# motorboard.net
KiCad netlist of a schematic drawn in EAGLE
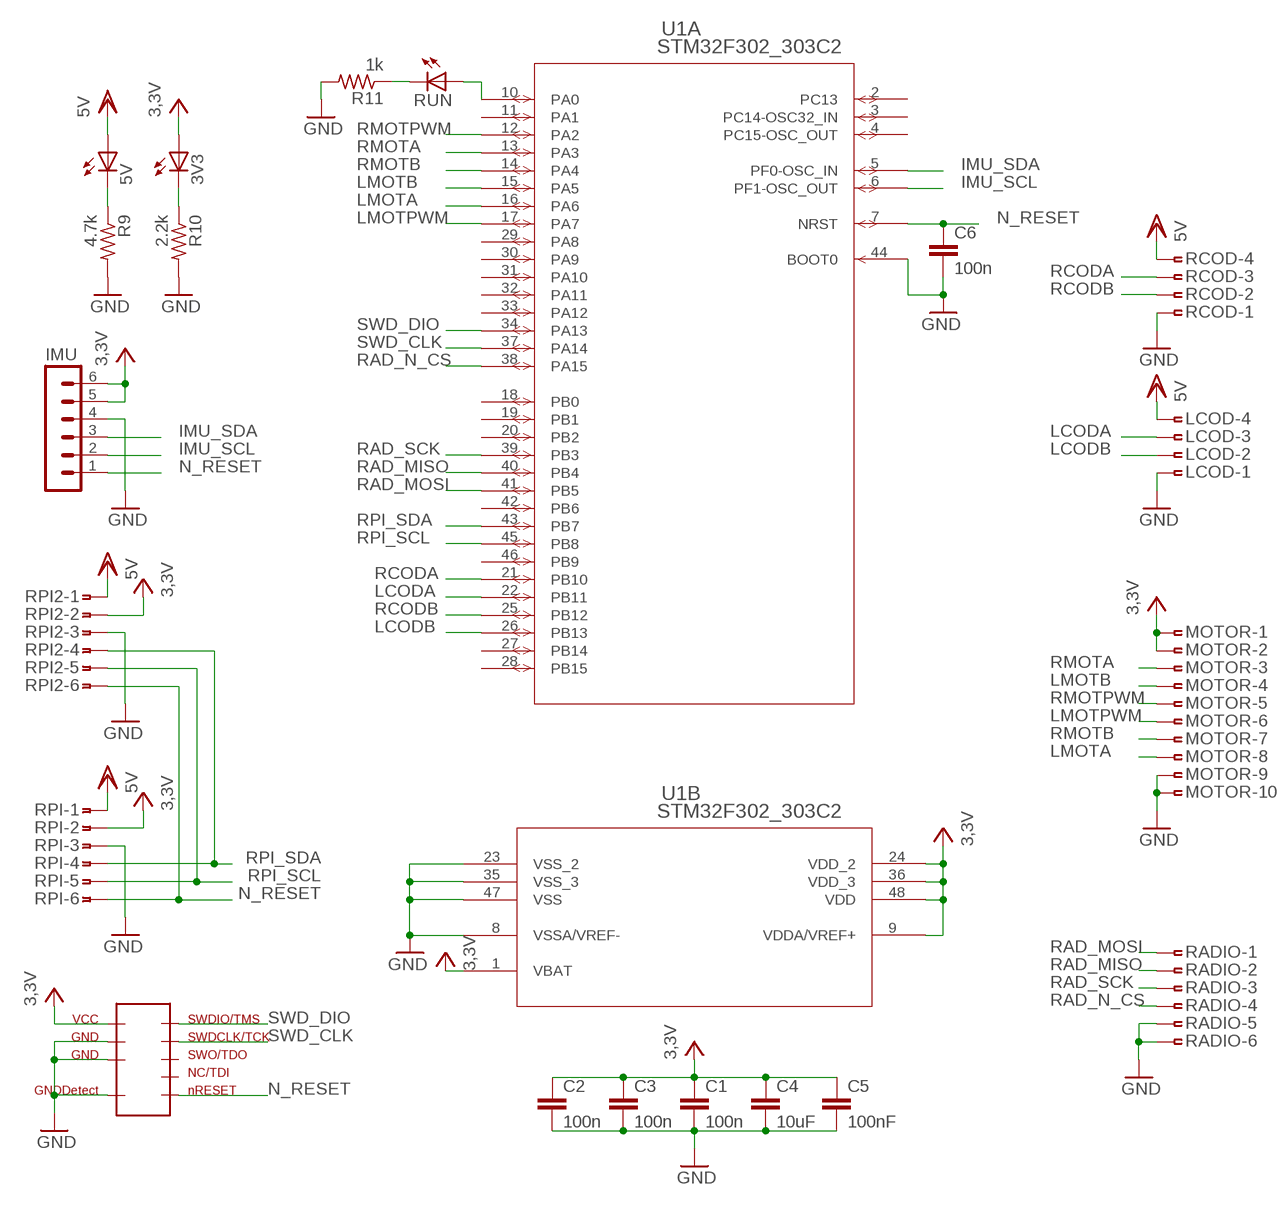
[diagram p0: schematic, sheet 1]

(export (version "E")
  (design (tool "Eeschema 10.0.6"))
  (components
    (comp (ref "3V3")
      (value "LEDCHIPLED_0805")
      (footprint "eagle-import:CHIPLED_0805")
      (libsource (lib "eagle-import") (part "LEDCHIPLED_0805"))
    )
    (comp (ref "5V")
      (value "LEDCHIPLED_0805")
      (footprint "eagle-import:CHIPLED_0805")
      (libsource (lib "eagle-import") (part "LEDCHIPLED_0805"))
    )
    (comp (ref "C1")
      (value "100n")
      (footprint "eagle-import:C0805")
      (libsource (lib "eagle-import") (part "C-EUC0805"))
    )
    (comp (ref "C2")
      (value "100n")
      (footprint "eagle-import:C0805")
      (libsource (lib "eagle-import") (part "C-EUC0805"))
    )
    (comp (ref "C3")
      (value "100n")
      (footprint "eagle-import:C0805")
      (libsource (lib "eagle-import") (part "C-EUC0805"))
    )
    (comp (ref "C4")
      (value "10uF")
      (footprint "eagle-import:C0805")
      (libsource (lib "eagle-import") (part "C-EUC0805"))
    )
    (comp (ref "C5")
      (value "100nF")
      (footprint "eagle-import:C0805")
      (libsource (lib "eagle-import") (part "C-EUC0805"))
    )
    (comp (ref "C6")
      (value "100n")
      (footprint "eagle-import:C0805")
      (libsource (lib "eagle-import") (part "C-EUC0805"))
    )
    (comp (ref "IMU")
      (value "MA06-1")
      (footprint "eagle-import:MA06-1")
      (libsource (lib "eagle-import") (part "MA06-1"))
    )
    (comp (ref "LCOD")
      (value "SMDTOP-4")
      (footprint "eagle-import:SMDTOP4")
      (libsource (lib "eagle-import") (part "SMDTOP-4"))
    )
    (comp (ref "MOTOR")
      (value "SMDTOP-10")
      (footprint "eagle-import:SMDTOP10")
      (libsource (lib "eagle-import") (part "SMDTOP-10"))
    )
    (comp (ref "R9")
      (value "4.7k")
      (footprint "eagle-import:M0805")
      (libsource (lib "eagle-import") (part "R-US_M0805"))
    )
    (comp (ref "R10")
      (value "2.2k")
      (footprint "eagle-import:M0805")
      (libsource (lib "eagle-import") (part "R-US_M0805"))
    )
    (comp (ref "R11")
      (value "1k")
      (footprint "eagle-import:M0805")
      (libsource (lib "eagle-import") (part "R-US_M0805"))
    )
    (comp (ref "RADIO")
      (value "SMDTOP-6")
      (footprint "eagle-import:SMDTOP6")
      (libsource (lib "eagle-import") (part "SMDTOP-6"))
    )
    (comp (ref "RCOD")
      (value "SMDTOP-4")
      (footprint "eagle-import:SMDTOP4")
      (libsource (lib "eagle-import") (part "SMDTOP-4"))
    )
    (comp (ref "RPI")
      (value "SMDTOP-6")
      (footprint "eagle-import:SMDTOP6")
      (libsource (lib "eagle-import") (part "SMDTOP-6"))
    )
    (comp (ref "RPI2")
      (value "SMDTOP-6")
      (footprint "eagle-import:SMDTOP6")
      (libsource (lib "eagle-import") (part "SMDTOP-6"))
    )
    (comp (ref "RUN")
      (value "LEDCHIPLED_0805")
      (footprint "eagle-import:CHIPLED_0805")
      (libsource (lib "eagle-import") (part "LEDCHIPLED_0805"))
    )
    (comp (ref "U$1")
      (value "SWD/JTAG-_PINS")
      (footprint "eagle-import:SAMTEC_SHF-105-01-L-D-SM")
      (libsource (lib "eagle-import") (part "SWD/JTAG-_PINS"))
    )
    (comp (ref "U1")
      (value "STM32F302_303C2")
      (footprint "eagle-import:LQFP48-7X7MM")
      (fields
        (field (name "MANUFACTURER_PART_NUMBER") "stm32f302_303c2")
        (field (name "COPYRIGHT") "Copyright C 2016 Accelerated Designs. All rights reserved")
      )
      (libsource (lib "eagle-import") (part "STM32F302_303C2"))
    )
  )
  (nets
    (net (code "1") (name "/IMU_SCL") (class "Default")
      (node (ref "IMU") (pin "2") (pinfunction "2_2") (pintype "passive"))
      (node (ref "U1") (pin "6") (pinfunction "PF1-OSC_OUT_6") (pintype "bidirectional"))
    )
    (net (code "2") (name "/IMU_SDA") (class "Default")
      (node (ref "IMU") (pin "3") (pinfunction "3_3") (pintype "passive"))
      (node (ref "U1") (pin "5") (pinfunction "PF0-OSC_IN_5") (pintype "bidirectional"))
    )
    (net (code "3") (name "/LCODA") (class "Default")
      (node (ref "LCOD") (pin "3") (pinfunction "1_3") (pintype "passive"))
      (node (ref "U1") (pin "22") (pinfunction "PB11_22") (pintype "bidirectional"))
    )
    (net (code "4") (name "/LCODB") (class "Default")
      (node (ref "LCOD") (pin "2") (pinfunction "1_2") (pintype "passive"))
      (node (ref "U1") (pin "26") (pinfunction "PB13_26") (pintype "bidirectional"))
    )
    (net (code "5") (name "/LMOTA") (class "Default")
      (node (ref "MOTOR") (pin "8") (pinfunction "1_8") (pintype "passive"))
      (node (ref "U1") (pin "16") (pinfunction "PA6_16") (pintype "bidirectional"))
    )
    (net (code "6") (name "/LMOTB") (class "Default")
      (node (ref "MOTOR") (pin "4") (pinfunction "1_4") (pintype "passive"))
      (node (ref "U1") (pin "15") (pinfunction "PA5_15") (pintype "bidirectional"))
    )
    (net (code "7") (name "/LMOTPWM") (class "Default")
      (node (ref "MOTOR") (pin "6") (pinfunction "1_6") (pintype "passive"))
      (node (ref "U1") (pin "17") (pinfunction "PA7_17") (pintype "bidirectional"))
    )
    (net (code "8") (name "/N_RESET") (class "Default")
      (node (ref "C6") (pin "1") (pinfunction "1_1") (pintype "passive"))
      (node (ref "IMU") (pin "1") (pinfunction "1_1") (pintype "passive"))
      (node (ref "RPI") (pin "6") (pinfunction "1_6") (pintype "passive"))
      (node (ref "RPI2") (pin "6") (pinfunction "1_6") (pintype "passive"))
      (node (ref "U$1") (pin "P$10") (pinfunction "P$10_P$10") (pintype "bidirectional"))
      (node (ref "U1") (pin "7") (pinfunction "NRST_7") (pintype "bidirectional"))
    )
    (net (code "9") (name "/RAD_MISO") (class "Default")
      (node (ref "RADIO") (pin "2") (pinfunction "1_2") (pintype "passive"))
      (node (ref "U1") (pin "40") (pinfunction "PB4_40") (pintype "bidirectional"))
    )
    (net (code "10") (name "/RAD_MOSI") (class "Default")
      (node (ref "RADIO") (pin "1") (pinfunction "1_1") (pintype "passive"))
      (node (ref "U1") (pin "41") (pinfunction "PB5_41") (pintype "bidirectional"))
    )
    (net (code "11") (name "/RAD_N_CS") (class "Default")
      (node (ref "RADIO") (pin "4") (pinfunction "1_4") (pintype "passive"))
      (node (ref "U1") (pin "38") (pinfunction "PA15_38") (pintype "bidirectional"))
    )
    (net (code "12") (name "/RAD_SCK") (class "Default")
      (node (ref "RADIO") (pin "3") (pinfunction "1_3") (pintype "passive"))
      (node (ref "U1") (pin "39") (pinfunction "PB3_39") (pintype "bidirectional"))
    )
    (net (code "13") (name "/RCODA") (class "Default")
      (node (ref "RCOD") (pin "3") (pinfunction "1_3") (pintype "passive"))
      (node (ref "U1") (pin "21") (pinfunction "PB10_21") (pintype "bidirectional"))
    )
    (net (code "14") (name "/RCODB") (class "Default")
      (node (ref "RCOD") (pin "2") (pinfunction "1_2") (pintype "passive"))
      (node (ref "U1") (pin "25") (pinfunction "PB12_25") (pintype "bidirectional"))
    )
    (net (code "15") (name "/RMOTA") (class "Default")
      (node (ref "MOTOR") (pin "3") (pinfunction "1_3") (pintype "passive"))
      (node (ref "U1") (pin "13") (pinfunction "PA3_13") (pintype "bidirectional"))
    )
    (net (code "16") (name "/RMOTB") (class "Default")
      (node (ref "MOTOR") (pin "7") (pinfunction "1_7") (pintype "passive"))
      (node (ref "U1") (pin "14") (pinfunction "PA4_14") (pintype "bidirectional"))
    )
    (net (code "17") (name "/RMOTPWM") (class "Default")
      (node (ref "MOTOR") (pin "5") (pinfunction "1_5") (pintype "passive"))
      (node (ref "U1") (pin "12") (pinfunction "PA2_12") (pintype "bidirectional"))
    )
    (net (code "18") (name "/RPI_SCL") (class "Default")
      (node (ref "RPI") (pin "5") (pinfunction "1_5") (pintype "passive"))
      (node (ref "RPI2") (pin "5") (pinfunction "1_5") (pintype "passive"))
      (node (ref "U1") (pin "45") (pinfunction "PB8_45") (pintype "bidirectional"))
    )
    (net (code "19") (name "/RPI_SDA") (class "Default")
      (node (ref "RPI") (pin "4") (pinfunction "1_4") (pintype "passive"))
      (node (ref "RPI2") (pin "4") (pinfunction "1_4") (pintype "passive"))
      (node (ref "U1") (pin "43") (pinfunction "PB7_43") (pintype "bidirectional"))
    )
    (net (code "20") (name "/SWD_CLK") (class "Default")
      (node (ref "U$1") (pin "P$4") (pinfunction "P$4_P$4") (pintype "bidirectional"))
      (node (ref "U1") (pin "37") (pinfunction "PA14_37") (pintype "bidirectional"))
    )
    (net (code "21") (name "/SWD_DIO") (class "Default")
      (node (ref "U$1") (pin "P$2") (pinfunction "P$2_P$2") (pintype "bidirectional"))
      (node (ref "U1") (pin "34") (pinfunction "PA13_34") (pintype "bidirectional"))
    )
    (net (code "22") (name "3,3V") (class "Default")
      (node (ref "3V3") (pin "A") (pinfunction "A_A") (pintype "passive"))
      (node (ref "C1") (pin "1") (pinfunction "1_1") (pintype "passive"))
      (node (ref "C2") (pin "1") (pinfunction "1_1") (pintype "passive"))
      (node (ref "C3") (pin "1") (pinfunction "1_1") (pintype "passive"))
      (node (ref "C4") (pin "1") (pinfunction "1_1") (pintype "passive"))
      (node (ref "C5") (pin "1") (pinfunction "1_1") (pintype "passive"))
      (node (ref "IMU") (pin "5") (pinfunction "5_5") (pintype "passive"))
      (node (ref "IMU") (pin "6") (pinfunction "6_6") (pintype "passive"))
      (node (ref "MOTOR") (pin "1") (pinfunction "1_1") (pintype "passive"))
      (node (ref "MOTOR") (pin "2") (pinfunction "1_2") (pintype "passive"))
      (node (ref "RPI") (pin "2") (pinfunction "1_2") (pintype "passive"))
      (node (ref "RPI2") (pin "2") (pinfunction "1_2") (pintype "passive"))
      (node (ref "U$1") (pin "P$1") (pinfunction "P$1_P$1") (pintype "bidirectional"))
      (node (ref "U1") (pin "1") (pinfunction "VBAT_1") (pintype "power_in"))
      (node (ref "U1") (pin "24") (pinfunction "VDD_2_24") (pintype "power_in"))
      (node (ref "U1") (pin "36") (pinfunction "VDD_3_36") (pintype "power_in"))
      (node (ref "U1") (pin "48") (pinfunction "VDD_48") (pintype "power_in"))
      (node (ref "U1") (pin "9") (pinfunction "VDDA/VREF+_9") (pintype "power_in"))
    )
    (net (code "23") (name "5V") (class "Default")
      (node (ref "5V") (pin "A") (pinfunction "A_A") (pintype "passive"))
      (node (ref "LCOD") (pin "4") (pinfunction "1_4") (pintype "passive"))
      (node (ref "RCOD") (pin "4") (pinfunction "1_4") (pintype "passive"))
      (node (ref "RPI") (pin "1") (pinfunction "1_1") (pintype "passive"))
      (node (ref "RPI2") (pin "1") (pinfunction "1_1") (pintype "passive"))
    )
    (net (code "24") (name "GND") (class "Default")
      (node (ref "C1") (pin "2") (pinfunction "2_2") (pintype "passive"))
      (node (ref "C2") (pin "2") (pinfunction "2_2") (pintype "passive"))
      (node (ref "C3") (pin "2") (pinfunction "2_2") (pintype "passive"))
      (node (ref "C4") (pin "2") (pinfunction "2_2") (pintype "passive"))
      (node (ref "C5") (pin "2") (pinfunction "2_2") (pintype "passive"))
      (node (ref "C6") (pin "2") (pinfunction "2_2") (pintype "passive"))
      (node (ref "IMU") (pin "4") (pinfunction "4_4") (pintype "passive"))
      (node (ref "LCOD") (pin "1") (pinfunction "1_1") (pintype "passive"))
      (node (ref "MOTOR") (pin "10") (pinfunction "1_10") (pintype "passive"))
      (node (ref "MOTOR") (pin "9") (pinfunction "1_9") (pintype "passive"))
      (node (ref "R10") (pin "2") (pinfunction "2_2") (pintype "passive"))
      (node (ref "R11") (pin "2") (pinfunction "2_2") (pintype "passive"))
      (node (ref "R9") (pin "2") (pinfunction "2_2") (pintype "passive"))
      (node (ref "RADIO") (pin "5") (pinfunction "1_5") (pintype "passive"))
      (node (ref "RADIO") (pin "6") (pinfunction "1_6") (pintype "passive"))
      (node (ref "RCOD") (pin "1") (pinfunction "1_1") (pintype "passive"))
      (node (ref "RPI") (pin "3") (pinfunction "1_3") (pintype "passive"))
      (node (ref "RPI2") (pin "3") (pinfunction "1_3") (pintype "passive"))
      (node (ref "U$1") (pin "P$3") (pinfunction "P$3_P$3") (pintype "bidirectional"))
      (node (ref "U$1") (pin "P$5") (pinfunction "P$5_P$5") (pintype "bidirectional"))
      (node (ref "U$1") (pin "P$9") (pinfunction "P$9_P$9") (pintype "bidirectional"))
      (node (ref "U1") (pin "23") (pinfunction "VSS_2_23") (pintype "power_in"))
      (node (ref "U1") (pin "35") (pinfunction "VSS_3_35") (pintype "power_in"))
      (node (ref "U1") (pin "44") (pinfunction "BOOT0_44") (pintype "input"))
      (node (ref "U1") (pin "47") (pinfunction "VSS_47") (pintype "power_in"))
      (node (ref "U1") (pin "8") (pinfunction "VSSA/VREF-_8") (pintype "power_in"))
    )
    (net (code "25") (name "Net-(3V3-PadC)") (class "Default")
      (node (ref "3V3") (pin "C") (pinfunction "C_C") (pintype "passive"))
      (node (ref "R10") (pin "1") (pinfunction "1_1") (pintype "passive"))
    )
    (net (code "26") (name "Net-(5V-PadC)") (class "Default")
      (node (ref "5V") (pin "C") (pinfunction "C_C") (pintype "passive"))
      (node (ref "R9") (pin "1") (pinfunction "1_1") (pintype "passive"))
    )
    (net (code "27") (name "Net-(R11-Pad1)") (class "Default")
      (node (ref "R11") (pin "1") (pinfunction "1_1") (pintype "passive"))
      (node (ref "RUN") (pin "C") (pinfunction "C_C") (pintype "passive"))
    )
    (net (code "28") (name "Net-(U1A-PA0)") (class "Default")
      (node (ref "RUN") (pin "A") (pinfunction "A_A") (pintype "passive"))
      (node (ref "U1") (pin "10") (pinfunction "PA0_10") (pintype "bidirectional"))
    )
    (net (code "29") (name "unconnected-(U$1-PadP$6)") (class "Default")
      (node (ref "U$1") (pin "P$6") (pinfunction "P$6_P$6") (pintype "bidirectional"))
    )
    (net (code "30") (name "unconnected-(U$1-PadP$8)") (class "Default")
      (node (ref "U$1") (pin "P$8") (pinfunction "P$8_P$8") (pintype "bidirectional"))
    )
    (net (code "31") (name "unconnected-(U1A-PA1-Pad11)") (class "Default")
      (node (ref "U1") (pin "11") (pinfunction "PA1_11") (pintype "bidirectional"))
    )
    (net (code "32") (name "unconnected-(U1A-PA8-Pad29)") (class "Default")
      (node (ref "U1") (pin "29") (pinfunction "PA8_29") (pintype "bidirectional"))
    )
    (net (code "33") (name "unconnected-(U1A-PA9-Pad30)") (class "Default")
      (node (ref "U1") (pin "30") (pinfunction "PA9_30") (pintype "bidirectional"))
    )
    (net (code "34") (name "unconnected-(U1A-PA10-Pad31)") (class "Default")
      (node (ref "U1") (pin "31") (pinfunction "PA10_31") (pintype "bidirectional"))
    )
    (net (code "35") (name "unconnected-(U1A-PA11-Pad32)") (class "Default")
      (node (ref "U1") (pin "32") (pinfunction "PA11_32") (pintype "bidirectional"))
    )
    (net (code "36") (name "unconnected-(U1A-PA12-Pad33)") (class "Default")
      (node (ref "U1") (pin "33") (pinfunction "PA12_33") (pintype "bidirectional"))
    )
    (net (code "37") (name "unconnected-(U1A-PB0-Pad18)") (class "Default")
      (node (ref "U1") (pin "18") (pinfunction "PB0_18") (pintype "bidirectional"))
    )
    (net (code "38") (name "unconnected-(U1A-PB1-Pad19)") (class "Default")
      (node (ref "U1") (pin "19") (pinfunction "PB1_19") (pintype "bidirectional"))
    )
    (net (code "39") (name "unconnected-(U1A-PB2-Pad20)") (class "Default")
      (node (ref "U1") (pin "20") (pinfunction "PB2_20") (pintype "bidirectional"))
    )
    (net (code "40") (name "unconnected-(U1A-PB6-Pad42)") (class "Default")
      (node (ref "U1") (pin "42") (pinfunction "PB6_42") (pintype "bidirectional"))
    )
    (net (code "41") (name "unconnected-(U1A-PB9-Pad46)") (class "Default")
      (node (ref "U1") (pin "46") (pinfunction "PB9_46") (pintype "bidirectional"))
    )
    (net (code "42") (name "unconnected-(U1A-PB14-Pad27)") (class "Default")
      (node (ref "U1") (pin "27") (pinfunction "PB14_27") (pintype "bidirectional"))
    )
    (net (code "43") (name "unconnected-(U1A-PB15-Pad28)") (class "Default")
      (node (ref "U1") (pin "28") (pinfunction "PB15_28") (pintype "bidirectional"))
    )
    (net (code "44") (name "unconnected-(U1A-PC13-Pad2)") (class "Default")
      (node (ref "U1") (pin "2") (pinfunction "PC13_2") (pintype "bidirectional"))
    )
    (net (code "45") (name "unconnected-(U1A-PC14-OSC32_IN-Pad3)") (class "Default")
      (node (ref "U1") (pin "3") (pinfunction "PC14-OSC32_IN_3") (pintype "bidirectional"))
    )
    (net (code "46") (name "unconnected-(U1A-PC15-OSC_OUT-Pad4)") (class "Default")
      (node (ref "U1") (pin "4") (pinfunction "PC15-OSC_OUT_4") (pintype "bidirectional"))
    )
  )
)
